# Instruction_Register.net
KiCad netlist of a schematic drawn in EAGLE
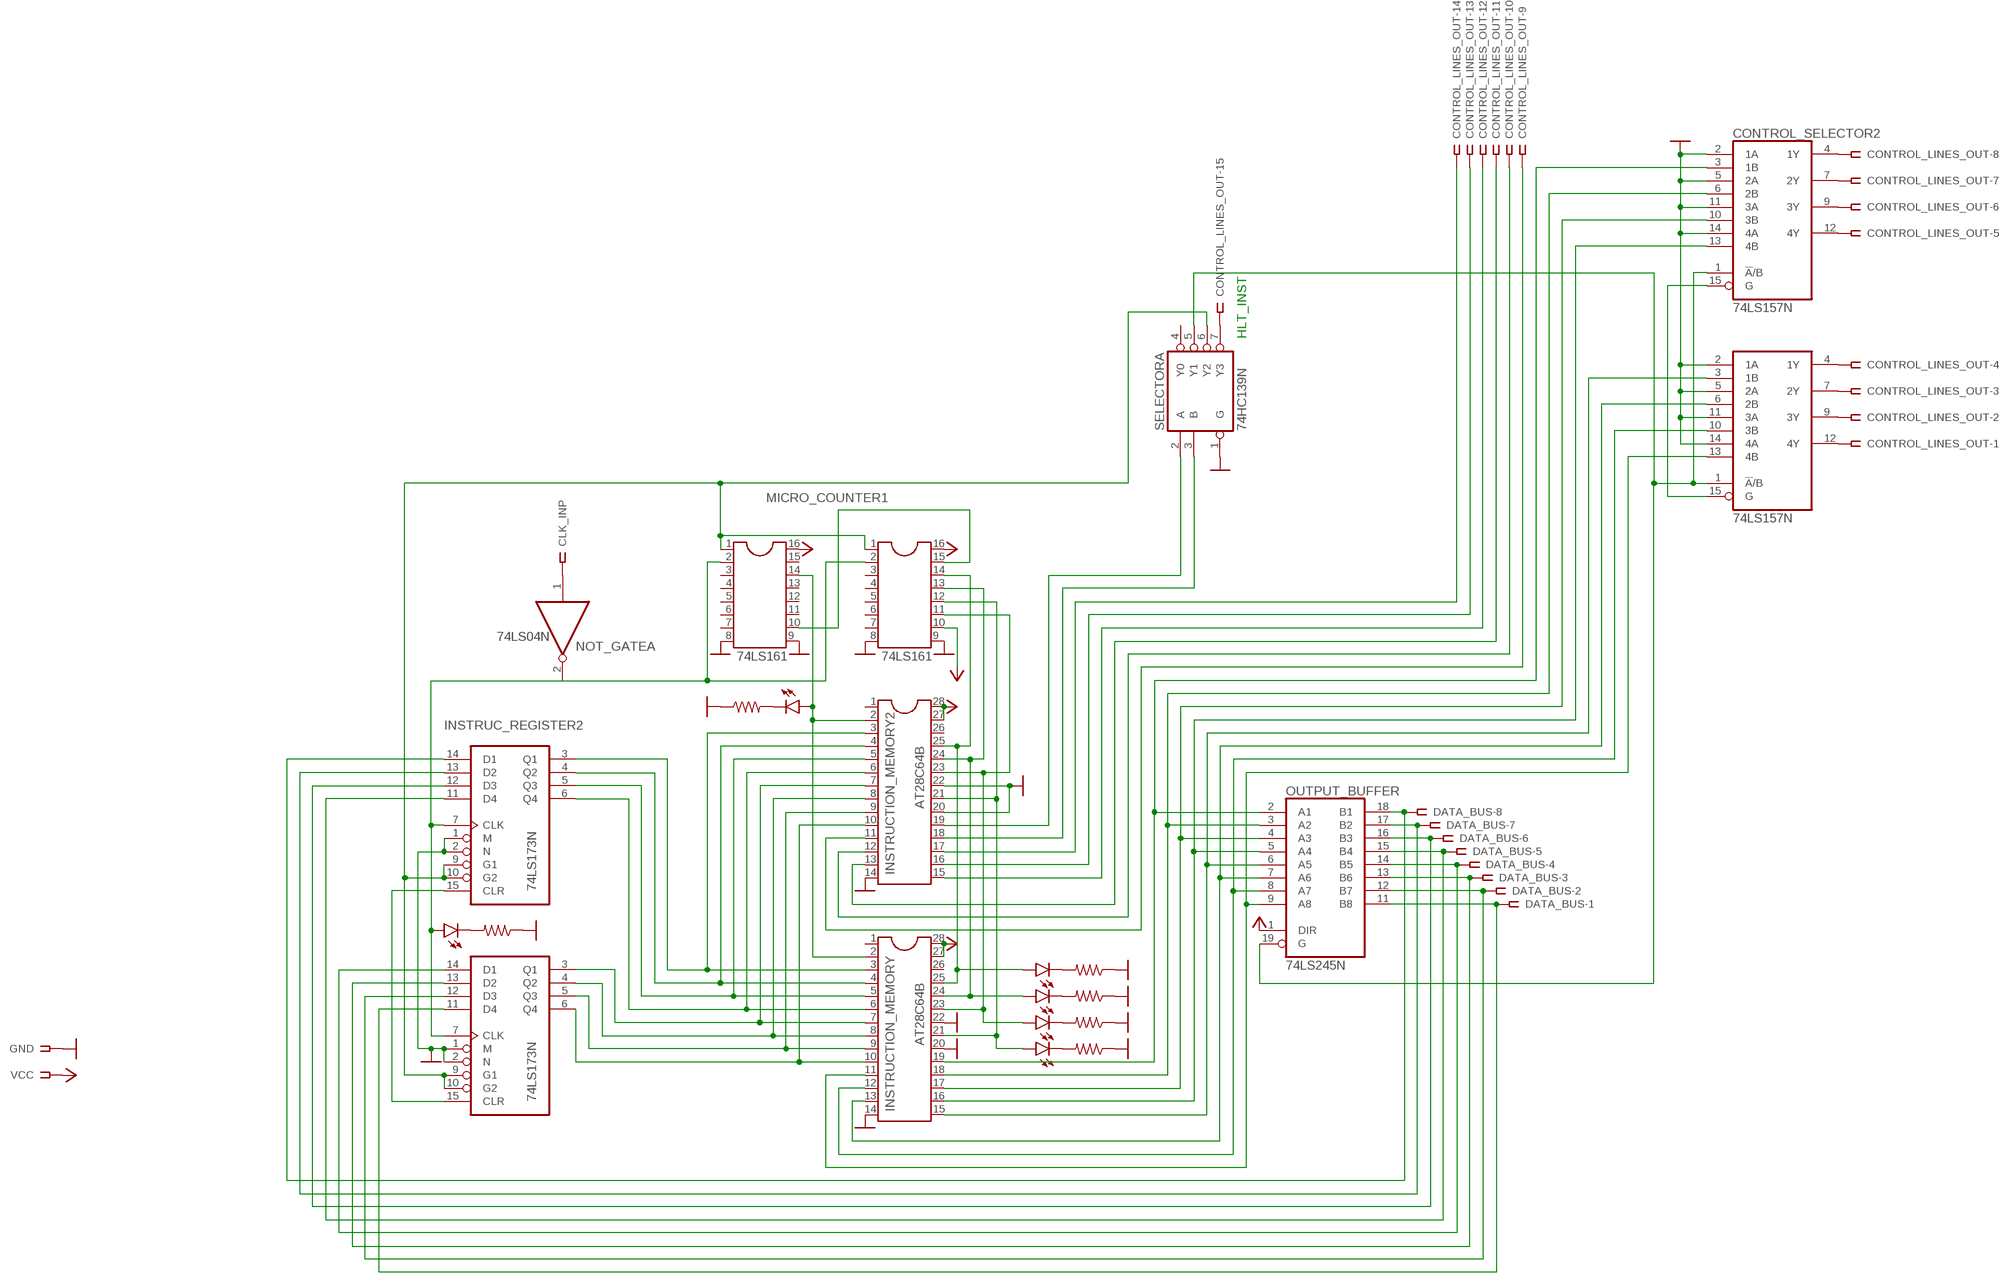
[diagram p0: schematic, sheet 1]

(export (version "E")
  (design (tool "Eeschema 10.0.6"))
  (components
    (comp (ref "CLK_INP")
      (value "SSW-101-02-G-S-RA")
      (footprint "eagle-import:SSW-101-02-G-S-RA")
      (fields (field (name "MF") "Samtec Inc."))
      (libsource (lib "eagle-import") (part "SSW-101-02-G-S-RA"))
    )
    (comp (ref "CONTROL_LINES_OUT")
      (value "SSW-115-02-G-S")
      (footprint "eagle-import:SSW-115-02-G-S")
      (fields (field (name "MF") "Samtec Inc."))
      (libsource (lib "eagle-import") (part "SSW-115-02-G-S"))
    )
    (comp (ref "CONTROL_SELECTOR")
      (value "74LS157N")
      (footprint "eagle-import:DIL16")
      (libsource (lib "eagle-import") (part "74157NLS"))
    )
    (comp (ref "CONTROL_SELECTOR2")
      (value "74LS157N")
      (footprint "eagle-import:DIL16")
      (libsource (lib "eagle-import") (part "74157NLS"))
    )
    (comp (ref "DATA_BUS")
      (value "SSW-108-02-G-S")
      (footprint "eagle-import:SSW-108-02-G-S")
      (fields (field (name "MF") "Samtec Inc."))
      (libsource (lib "eagle-import") (part "SSW-108-02-G-S"))
    )
    (comp (ref "GND")
      (value "SSW-101-02-G-S-RA")
      (footprint "eagle-import:SSW-101-02-G-S-RA")
      (fields (field (name "MF") "Samtec Inc."))
      (libsource (lib "eagle-import") (part "SSW-101-02-G-S-RA"))
    )
    (comp (ref "INSTRUCTION_MEMORY")
      (value "AT28C64B")
      (footprint "eagle-import:DIL28-6")
      (libsource (lib "eagle-import") (part "DIL28"))
    )
    (comp (ref "INSTRUCTION_MEMORY2")
      (value "AT28C64B")
      (footprint "eagle-import:DIL28-6")
      (libsource (lib "eagle-import") (part "DIL28"))
    )
    (comp (ref "INSTRUC_REGISTER2")
      (value "74LS173N")
      (footprint "eagle-import:DIL16")
      (libsource (lib "eagle-import") (part "74173NLS"))
    )
    (comp (ref "INVERTED_CLK")
      (value "LED5MM")
      (footprint "eagle-import:LED5MM")
      (libsource (lib "eagle-import") (part "LED5MM"))
    )
    (comp (ref "I_ADDRESS_REGISTER")
      (value "74LS173N")
      (footprint "eagle-import:DIL16")
      (libsource (lib "eagle-import") (part "74173NLS"))
    )
    (comp (ref "LED18")
      (value "LED5MM")
      (footprint "eagle-import:LED5MM")
      (libsource (lib "eagle-import") (part "LED5MM"))
    )
    (comp (ref "LED19")
      (value "LED5MM")
      (footprint "eagle-import:LED5MM")
      (libsource (lib "eagle-import") (part "LED5MM"))
    )
    (comp (ref "LED20")
      (value "LED5MM")
      (footprint "eagle-import:LED5MM")
      (libsource (lib "eagle-import") (part "LED5MM"))
    )
    (comp (ref "LED21")
      (value "LED5MM")
      (footprint "eagle-import:LED5MM")
      (libsource (lib "eagle-import") (part "LED5MM"))
    )
    (comp (ref "LED22")
      (value "LED5MM")
      (footprint "eagle-import:LED5MM")
      (libsource (lib "eagle-import") (part "LED5MM"))
    )
    (comp (ref "MICRO_COUNTER")
      (value "74LS161")
      (footprint "eagle-import:DIL16")
      (libsource (lib "eagle-import") (part "DIL16"))
    )
    (comp (ref "MICRO_COUNTER1")
      (value "74LS161")
      (footprint "eagle-import:DIL16")
      (libsource (lib "eagle-import") (part "DIL16"))
    )
    (comp (ref "NOT_GATE")
      (value "74LS04N")
      (footprint "eagle-import:DIL14")
      (libsource (lib "eagle-import") (part "7404NLS"))
    )
    (comp (ref "OUTPUT_BUFFER")
      (value "74LS245N")
      (footprint "eagle-import:DIL20")
      (libsource (lib "eagle-import") (part "74245NLS"))
    )
    (comp (ref "R1")
      (value "~220")
      (footprint "eagle-import:0204_7")
      (libsource (lib "eagle-import") (part "R-US_0204/7"))
    )
    (comp (ref "R18")
      (value "~220")
      (footprint "eagle-import:0204_7")
      (libsource (lib "eagle-import") (part "R-US_0204/7"))
    )
    (comp (ref "R19")
      (value "~220")
      (footprint "eagle-import:0204_7")
      (libsource (lib "eagle-import") (part "R-US_0204/7"))
    )
    (comp (ref "R20")
      (value "~220")
      (footprint "eagle-import:0204_7")
      (libsource (lib "eagle-import") (part "R-US_0204/7"))
    )
    (comp (ref "R21")
      (value "~220")
      (footprint "eagle-import:0204_7")
      (libsource (lib "eagle-import") (part "R-US_0204/7"))
    )
    (comp (ref "R22")
      (value "~220")
      (footprint "eagle-import:0204_7")
      (libsource (lib "eagle-import") (part "R-US_0204/7"))
    )
    (comp (ref "SELECTOR")
      (value "74HC139N")
      (footprint "eagle-import:DIL16")
      (libsource (lib "eagle-import") (part "74139NHC"))
    )
    (comp (ref "VCC")
      (value "SSW-101-02-G-S-RA")
      (footprint "eagle-import:SSW-101-02-G-S-RA")
      (fields (field (name "MF") "Samtec Inc."))
      (libsource (lib "eagle-import") (part "SSW-101-02-G-S-RA"))
    )
  )
  (nets
    (net (code "1") (name "GND") (class "Default")
      (node (ref "CONTROL_SELECTOR") (pin "11") (pinfunction "3A_11") (pintype "input"))
      (node (ref "CONTROL_SELECTOR") (pin "14") (pinfunction "4A_14") (pintype "input"))
      (node (ref "CONTROL_SELECTOR") (pin "2") (pinfunction "1A_2") (pintype "input"))
      (node (ref "CONTROL_SELECTOR") (pin "5") (pinfunction "2A_5") (pintype "input"))
      (node (ref "CONTROL_SELECTOR2") (pin "11") (pinfunction "3A_11") (pintype "input"))
      (node (ref "CONTROL_SELECTOR2") (pin "14") (pinfunction "4A_14") (pintype "input"))
      (node (ref "CONTROL_SELECTOR2") (pin "2") (pinfunction "1A_2") (pintype "input"))
      (node (ref "CONTROL_SELECTOR2") (pin "5") (pinfunction "2A_5") (pintype "input"))
      (node (ref "GND") (pin "1") (pinfunction "1_1") (pintype "passive"))
      (node (ref "INSTRUCTION_MEMORY") (pin "14") (pinfunction "14_14") (pintype "passive"))
      (node (ref "INSTRUCTION_MEMORY") (pin "20") (pinfunction "20_20") (pintype "passive"))
      (node (ref "INSTRUCTION_MEMORY") (pin "22") (pinfunction "22_22") (pintype "passive"))
      (node (ref "INSTRUCTION_MEMORY2") (pin "14") (pinfunction "14_14") (pintype "passive"))
      (node (ref "INSTRUCTION_MEMORY2") (pin "20") (pinfunction "20_20") (pintype "passive"))
      (node (ref "INSTRUCTION_MEMORY2") (pin "22") (pinfunction "22_22") (pintype "passive"))
      (node (ref "INSTRUC_REGISTER2") (pin "1") (pinfunction "M_1") (pintype "input"))
      (node (ref "INSTRUC_REGISTER2") (pin "2") (pinfunction "N_2") (pintype "input"))
      (node (ref "I_ADDRESS_REGISTER") (pin "1") (pinfunction "M_1") (pintype "input"))
      (node (ref "I_ADDRESS_REGISTER") (pin "2") (pinfunction "N_2") (pintype "input"))
      (node (ref "MICRO_COUNTER") (pin "8") (pinfunction "8_8") (pintype "passive"))
      (node (ref "MICRO_COUNTER") (pin "9") (pinfunction "9_9") (pintype "passive"))
      (node (ref "MICRO_COUNTER1") (pin "8") (pinfunction "8_8") (pintype "passive"))
      (node (ref "MICRO_COUNTER1") (pin "9") (pinfunction "9_9") (pintype "passive"))
      (node (ref "R1") (pin "1") (pinfunction "1_1") (pintype "passive"))
      (node (ref "R18") (pin "1") (pinfunction "1_1") (pintype "passive"))
      (node (ref "R19") (pin "1") (pinfunction "1_1") (pintype "passive"))
      (node (ref "R20") (pin "1") (pinfunction "1_1") (pintype "passive"))
      (node (ref "R21") (pin "1") (pinfunction "1_1") (pintype "passive"))
      (node (ref "R22") (pin "1") (pinfunction "1_1") (pintype "passive"))
      (node (ref "SELECTOR") (pin "1") (pinfunction "G_1") (pintype "input"))
    )
    (net (code "2") (name "Net-(CONTROL_LINES_OUTB-1)") (class "Default")
      (node (ref "CONTROL_LINES_OUT") (pin "10") (pinfunction "1_10") (pintype "passive"))
      (node (ref "INSTRUCTION_MEMORY2") (pin "12") (pinfunction "12_12") (pintype "passive"))
    )
    (net (code "3") (name "Net-(CONTROL_LINES_OUTC-1)") (class "Default")
      (node (ref "CONTROL_LINES_OUT") (pin "11") (pinfunction "1_11") (pintype "passive"))
      (node (ref "INSTRUCTION_MEMORY2") (pin "13") (pinfunction "13_13") (pintype "passive"))
    )
    (net (code "4") (name "Net-(CONTROL_LINES_OUTD-1)") (class "Default")
      (node (ref "CONTROL_LINES_OUT") (pin "12") (pinfunction "1_12") (pintype "passive"))
      (node (ref "INSTRUCTION_MEMORY2") (pin "15") (pinfunction "15_15") (pintype "passive"))
    )
    (net (code "5") (name "Net-(CONTROL_LINES_OUTE-1)") (class "Default")
      (node (ref "CONTROL_LINES_OUT") (pin "13") (pinfunction "1_13") (pintype "passive"))
      (node (ref "INSTRUCTION_MEMORY2") (pin "16") (pinfunction "16_16") (pintype "passive"))
    )
    (net (code "6") (name "Net-(CONTROL_LINES_OUTF-1)") (class "Default")
      (node (ref "CONTROL_LINES_OUT") (pin "14") (pinfunction "1_14") (pintype "passive"))
      (node (ref "INSTRUCTION_MEMORY2") (pin "17") (pinfunction "17_17") (pintype "passive"))
    )
    (net (code "7") (name "Net-(CONTROL_LINES_OUTG-1)") (class "Default")
      (node (ref "CONTROL_LINES_OUT") (pin "15") (pinfunction "1_15") (pintype "passive"))
      (node (ref "SELECTOR") (pin "7") (pinfunction "Y3_7") (pintype "output"))
    )
    (net (code "8") (name "Net-(CONTROL_LINES_OUTH-1)") (class "Default")
      (node (ref "CONTROL_LINES_OUT") (pin "2") (pinfunction "1_2") (pintype "passive"))
      (node (ref "CONTROL_SELECTOR") (pin "9") (pinfunction "3Y_9") (pintype "output"))
    )
    (net (code "9") (name "Net-(CONTROL_LINES_OUTI-1)") (class "Default")
      (node (ref "CONTROL_LINES_OUT") (pin "3") (pinfunction "1_3") (pintype "passive"))
      (node (ref "CONTROL_SELECTOR") (pin "7") (pinfunction "2Y_7") (pintype "output"))
    )
    (net (code "10") (name "Net-(CONTROL_LINES_OUTJ-1)") (class "Default")
      (node (ref "CONTROL_LINES_OUT") (pin "4") (pinfunction "1_4") (pintype "passive"))
      (node (ref "CONTROL_SELECTOR") (pin "4") (pinfunction "1Y_4") (pintype "output"))
    )
    (net (code "11") (name "Net-(CONTROL_LINES_OUTK-1)") (class "Default")
      (node (ref "CONTROL_LINES_OUT") (pin "5") (pinfunction "1_5") (pintype "passive"))
      (node (ref "CONTROL_SELECTOR2") (pin "12") (pinfunction "4Y_12") (pintype "output"))
    )
    (net (code "12") (name "Net-(CONTROL_LINES_OUTL-1)") (class "Default")
      (node (ref "CONTROL_LINES_OUT") (pin "6") (pinfunction "1_6") (pintype "passive"))
      (node (ref "CONTROL_SELECTOR2") (pin "9") (pinfunction "3Y_9") (pintype "output"))
    )
    (net (code "13") (name "Net-(CONTROL_LINES_OUTM-1)") (class "Default")
      (node (ref "CONTROL_LINES_OUT") (pin "7") (pinfunction "1_7") (pintype "passive"))
      (node (ref "CONTROL_SELECTOR2") (pin "7") (pinfunction "2Y_7") (pintype "output"))
    )
    (net (code "14") (name "Net-(CONTROL_LINES_OUTN-1)") (class "Default")
      (node (ref "CONTROL_LINES_OUT") (pin "8") (pinfunction "1_8") (pintype "passive"))
      (node (ref "CONTROL_SELECTOR2") (pin "4") (pinfunction "1Y_4") (pintype "output"))
    )
    (net (code "15") (name "Net-(CONTROL_LINES_OUTO-1)") (class "Default")
      (node (ref "CONTROL_LINES_OUT") (pin "9") (pinfunction "1_9") (pintype "passive"))
      (node (ref "INSTRUCTION_MEMORY2") (pin "11") (pinfunction "11_11") (pintype "passive"))
    )
    (net (code "16") (name "Net-(CONTROL_SELECTOR2A-1B)") (class "Default")
      (node (ref "CONTROL_SELECTOR2") (pin "3") (pinfunction "1B_3") (pintype "input"))
      (node (ref "INSTRUCTION_MEMORY") (pin "19") (pinfunction "19_19") (pintype "passive"))
      (node (ref "OUTPUT_BUFFER") (pin "2") (pinfunction "A1_2") (pintype "bidirectional"))
    )
    (net (code "17") (name "Net-(CONTROL_SELECTOR2A-2B)") (class "Default")
      (node (ref "CONTROL_SELECTOR2") (pin "6") (pinfunction "2B_6") (pintype "input"))
      (node (ref "INSTRUCTION_MEMORY") (pin "18") (pinfunction "18_18") (pintype "passive"))
      (node (ref "OUTPUT_BUFFER") (pin "3") (pinfunction "A2_3") (pintype "bidirectional"))
    )
    (net (code "18") (name "Net-(CONTROL_SELECTOR2A-3B)") (class "Default")
      (node (ref "CONTROL_SELECTOR2") (pin "10") (pinfunction "3B_10") (pintype "input"))
      (node (ref "INSTRUCTION_MEMORY") (pin "17") (pinfunction "17_17") (pintype "passive"))
      (node (ref "OUTPUT_BUFFER") (pin "4") (pinfunction "A3_4") (pintype "bidirectional"))
    )
    (net (code "19") (name "Net-(CONTROL_SELECTOR2A-4B)") (class "Default")
      (node (ref "CONTROL_SELECTOR2") (pin "13") (pinfunction "4B_13") (pintype "input"))
      (node (ref "INSTRUCTION_MEMORY") (pin "16") (pinfunction "16_16") (pintype "passive"))
      (node (ref "OUTPUT_BUFFER") (pin "5") (pinfunction "A4_5") (pintype "bidirectional"))
    )
    (net (code "20") (name "Net-(CONTROL_SELECTOR2A-G)") (class "Default")
      (node (ref "CONTROL_SELECTOR") (pin "15") (pinfunction "G_15") (pintype "input"))
      (node (ref "CONTROL_SELECTOR2") (pin "15") (pinfunction "G_15") (pintype "input"))
    )
    (net (code "21") (name "Net-(CONTROL_SELECTOR2A-~{A}{slash}B)") (class "Default")
      (node (ref "CONTROL_SELECTOR") (pin "1") (pinfunction "~{A}/B_1") (pintype "input"))
      (node (ref "CONTROL_SELECTOR2") (pin "1") (pinfunction "~{A}/B_1") (pintype "input"))
      (node (ref "OUTPUT_BUFFER") (pin "19") (pinfunction "G_19") (pintype "input"))
      (node (ref "SELECTOR") (pin "5") (pinfunction "Y1_5") (pintype "output"))
    )
    (net (code "22") (name "Net-(CONTROL_SELECTORA-1B)") (class "Default")
      (node (ref "CONTROL_SELECTOR") (pin "3") (pinfunction "1B_3") (pintype "input"))
      (node (ref "INSTRUCTION_MEMORY") (pin "15") (pinfunction "15_15") (pintype "passive"))
      (node (ref "OUTPUT_BUFFER") (pin "6") (pinfunction "A5_6") (pintype "bidirectional"))
    )
    (net (code "23") (name "Net-(CONTROL_SELECTORA-2B)") (class "Default")
      (node (ref "CONTROL_SELECTOR") (pin "6") (pinfunction "2B_6") (pintype "input"))
      (node (ref "INSTRUCTION_MEMORY") (pin "13") (pinfunction "13_13") (pintype "passive"))
      (node (ref "OUTPUT_BUFFER") (pin "7") (pinfunction "A6_7") (pintype "bidirectional"))
    )
    (net (code "24") (name "Net-(CONTROL_SELECTORA-3B)") (class "Default")
      (node (ref "CONTROL_SELECTOR") (pin "10") (pinfunction "3B_10") (pintype "input"))
      (node (ref "INSTRUCTION_MEMORY") (pin "12") (pinfunction "12_12") (pintype "passive"))
      (node (ref "OUTPUT_BUFFER") (pin "8") (pinfunction "A7_8") (pintype "bidirectional"))
    )
    (net (code "25") (name "Net-(CONTROL_SELECTORA-4B)") (class "Default")
      (node (ref "CONTROL_SELECTOR") (pin "13") (pinfunction "4B_13") (pintype "input"))
      (node (ref "INSTRUCTION_MEMORY") (pin "11") (pinfunction "11_11") (pintype "passive"))
      (node (ref "OUTPUT_BUFFER") (pin "9") (pinfunction "A8_9") (pintype "bidirectional"))
    )
    (net (code "26") (name "Net-(CONTROL_SELECTORA-4Y)") (class "Default")
      (node (ref "CONTROL_LINES_OUT") (pin "1") (pinfunction "1_1") (pintype "passive"))
      (node (ref "CONTROL_SELECTOR") (pin "12") (pinfunction "4Y_12") (pintype "output"))
    )
    (net (code "27") (name "Net-(DATA_BUSB-1)") (class "Default")
      (node (ref "DATA_BUS") (pin "2") (pinfunction "1_2") (pintype "passive"))
      (node (ref "I_ADDRESS_REGISTER") (pin "12") (pinfunction "D3_12") (pintype "input"))
      (node (ref "OUTPUT_BUFFER") (pin "12") (pinfunction "B7_12") (pintype "bidirectional"))
    )
    (net (code "28") (name "Net-(DATA_BUSC-1)") (class "Default")
      (node (ref "DATA_BUS") (pin "3") (pinfunction "1_3") (pintype "passive"))
      (node (ref "I_ADDRESS_REGISTER") (pin "13") (pinfunction "D2_13") (pintype "input"))
      (node (ref "OUTPUT_BUFFER") (pin "13") (pinfunction "B6_13") (pintype "bidirectional"))
    )
    (net (code "29") (name "Net-(DATA_BUSD-1)") (class "Default")
      (node (ref "DATA_BUS") (pin "4") (pinfunction "1_4") (pintype "passive"))
      (node (ref "I_ADDRESS_REGISTER") (pin "14") (pinfunction "D1_14") (pintype "input"))
      (node (ref "OUTPUT_BUFFER") (pin "14") (pinfunction "B5_14") (pintype "bidirectional"))
    )
    (net (code "30") (name "Net-(DATA_BUSE-1)") (class "Default")
      (node (ref "DATA_BUS") (pin "5") (pinfunction "1_5") (pintype "passive"))
      (node (ref "INSTRUC_REGISTER2") (pin "11") (pinfunction "D4_11") (pintype "input"))
      (node (ref "OUTPUT_BUFFER") (pin "15") (pinfunction "B4_15") (pintype "bidirectional"))
    )
    (net (code "31") (name "Net-(DATA_BUSF-1)") (class "Default")
      (node (ref "DATA_BUS") (pin "6") (pinfunction "1_6") (pintype "passive"))
      (node (ref "INSTRUC_REGISTER2") (pin "12") (pinfunction "D3_12") (pintype "input"))
      (node (ref "OUTPUT_BUFFER") (pin "16") (pinfunction "B3_16") (pintype "bidirectional"))
    )
    (net (code "32") (name "Net-(DATA_BUSG-1)") (class "Default")
      (node (ref "DATA_BUS") (pin "7") (pinfunction "1_7") (pintype "passive"))
      (node (ref "INSTRUC_REGISTER2") (pin "13") (pinfunction "D2_13") (pintype "input"))
      (node (ref "OUTPUT_BUFFER") (pin "17") (pinfunction "B2_17") (pintype "bidirectional"))
    )
    (net (code "33") (name "Net-(DATA_BUSH-1)") (class "Default")
      (node (ref "DATA_BUS") (pin "8") (pinfunction "1_8") (pintype "passive"))
      (node (ref "INSTRUC_REGISTER2") (pin "14") (pinfunction "D1_14") (pintype "input"))
      (node (ref "OUTPUT_BUFFER") (pin "18") (pinfunction "B1_18") (pintype "bidirectional"))
    )
    (net (code "34") (name "Net-(INSTRUCTION_MEMORY-Pad2)") (class "Default")
      (node (ref "INSTRUCTION_MEMORY") (pin "2") (pinfunction "2_2") (pintype "passive"))
      (node (ref "INSTRUCTION_MEMORY2") (pin "2") (pinfunction "2_2") (pintype "passive"))
      (node (ref "LED22") (pin "A") (pinfunction "A_A") (pintype "passive"))
      (node (ref "MICRO_COUNTER1") (pin "14") (pinfunction "14_14") (pintype "passive"))
    )
    (net (code "35") (name "Net-(INSTRUCTION_MEMORY-Pad21)") (class "Default")
      (node (ref "INSTRUCTION_MEMORY") (pin "21") (pinfunction "21_21") (pintype "passive"))
      (node (ref "INSTRUCTION_MEMORY2") (pin "21") (pinfunction "21_21") (pintype "passive"))
      (node (ref "LED21") (pin "A") (pinfunction "A_A") (pintype "passive"))
      (node (ref "MICRO_COUNTER") (pin "12") (pinfunction "12_12") (pintype "passive"))
    )
    (net (code "36") (name "Net-(INSTRUCTION_MEMORY-Pad23)") (class "Default")
      (node (ref "INSTRUCTION_MEMORY") (pin "23") (pinfunction "23_23") (pintype "passive"))
      (node (ref "INSTRUCTION_MEMORY2") (pin "23") (pinfunction "23_23") (pintype "passive"))
      (node (ref "LED20") (pin "A") (pinfunction "A_A") (pintype "passive"))
      (node (ref "MICRO_COUNTER") (pin "11") (pinfunction "11_11") (pintype "passive"))
    )
    (net (code "37") (name "Net-(INSTRUCTION_MEMORY-Pad24)") (class "Default")
      (node (ref "INSTRUCTION_MEMORY") (pin "24") (pinfunction "24_24") (pintype "passive"))
      (node (ref "INSTRUCTION_MEMORY2") (pin "24") (pinfunction "24_24") (pintype "passive"))
      (node (ref "LED19") (pin "A") (pinfunction "A_A") (pintype "passive"))
      (node (ref "MICRO_COUNTER") (pin "13") (pinfunction "13_13") (pintype "passive"))
    )
    (net (code "38") (name "Net-(INSTRUCTION_MEMORY-Pad25)") (class "Default")
      (node (ref "INSTRUCTION_MEMORY") (pin "25") (pinfunction "25_25") (pintype "passive"))
      (node (ref "INSTRUCTION_MEMORY2") (pin "25") (pinfunction "25_25") (pintype "passive"))
      (node (ref "LED18") (pin "A") (pinfunction "A_A") (pintype "passive"))
      (node (ref "MICRO_COUNTER") (pin "14") (pinfunction "14_14") (pintype "passive"))
    )
    (net (code "39") (name "Net-(INSTRUC_REGISTER2A-CLK)") (class "Default")
      (node (ref "INSTRUC_REGISTER2") (pin "7") (pinfunction "CLK_7") (pintype "input"))
      (node (ref "INVERTED_CLK") (pin "A") (pinfunction "A_A") (pintype "passive"))
      (node (ref "I_ADDRESS_REGISTER") (pin "7") (pinfunction "CLK_7") (pintype "input"))
      (node (ref "MICRO_COUNTER") (pin "2") (pinfunction "2_2") (pintype "passive"))
      (node (ref "MICRO_COUNTER1") (pin "2") (pinfunction "2_2") (pintype "passive"))
      (node (ref "NOT_GATE") (pin "2") (pinfunction "O_2") (pintype "output"))
    )
    (net (code "40") (name "Net-(INSTRUC_REGISTER2A-CLR)") (class "Default")
      (node (ref "INSTRUC_REGISTER2") (pin "15") (pinfunction "CLR_15") (pintype "input"))
      (node (ref "I_ADDRESS_REGISTER") (pin "15") (pinfunction "CLR_15") (pintype "input"))
    )
    (net (code "41") (name "Net-(INSTRUC_REGISTER2A-G1)") (class "Default")
      (node (ref "INSTRUC_REGISTER2") (pin "10") (pinfunction "G2_10") (pintype "input"))
      (node (ref "INSTRUC_REGISTER2") (pin "9") (pinfunction "G1_9") (pintype "input"))
      (node (ref "I_ADDRESS_REGISTER") (pin "10") (pinfunction "G2_10") (pintype "input"))
      (node (ref "I_ADDRESS_REGISTER") (pin "9") (pinfunction "G1_9") (pintype "input"))
      (node (ref "MICRO_COUNTER") (pin "1") (pinfunction "1_1") (pintype "passive"))
      (node (ref "MICRO_COUNTER1") (pin "1") (pinfunction "1_1") (pintype "passive"))
      (node (ref "SELECTOR") (pin "6") (pinfunction "Y2_6") (pintype "output"))
    )
    (net (code "42") (name "Net-(INSTRUC_REGISTER2A-Q1)") (class "Default")
      (node (ref "INSTRUCTION_MEMORY") (pin "3") (pinfunction "3_3") (pintype "passive"))
      (node (ref "INSTRUCTION_MEMORY2") (pin "3") (pinfunction "3_3") (pintype "passive"))
      (node (ref "INSTRUC_REGISTER2") (pin "3") (pinfunction "Q1_3") (pintype "tri_state"))
    )
    (net (code "43") (name "Net-(INSTRUC_REGISTER2A-Q2)") (class "Default")
      (node (ref "INSTRUCTION_MEMORY") (pin "4") (pinfunction "4_4") (pintype "passive"))
      (node (ref "INSTRUCTION_MEMORY2") (pin "4") (pinfunction "4_4") (pintype "passive"))
      (node (ref "INSTRUC_REGISTER2") (pin "4") (pinfunction "Q2_4") (pintype "tri_state"))
    )
    (net (code "44") (name "Net-(INSTRUC_REGISTER2A-Q3)") (class "Default")
      (node (ref "INSTRUCTION_MEMORY") (pin "5") (pinfunction "5_5") (pintype "passive"))
      (node (ref "INSTRUCTION_MEMORY2") (pin "5") (pinfunction "5_5") (pintype "passive"))
      (node (ref "INSTRUC_REGISTER2") (pin "5") (pinfunction "Q3_5") (pintype "tri_state"))
    )
    (net (code "45") (name "Net-(INSTRUC_REGISTER2A-Q4)") (class "Default")
      (node (ref "INSTRUCTION_MEMORY") (pin "6") (pinfunction "6_6") (pintype "passive"))
      (node (ref "INSTRUCTION_MEMORY2") (pin "6") (pinfunction "6_6") (pintype "passive"))
      (node (ref "INSTRUC_REGISTER2") (pin "6") (pinfunction "Q4_6") (pintype "tri_state"))
    )
    (net (code "46") (name "Net-(INVERTED_CLK-C)") (class "Default")
      (node (ref "INVERTED_CLK") (pin "K") (pinfunction "C_K") (pintype "passive"))
      (node (ref "R1") (pin "2") (pinfunction "2_2") (pintype "passive"))
    )
    (net (code "47") (name "Net-(I_ADDRESS_REGISTERA-D4)") (class "Default")
      (node (ref "DATA_BUS") (pin "1") (pinfunction "1_1") (pintype "passive"))
      (node (ref "I_ADDRESS_REGISTER") (pin "11") (pinfunction "D4_11") (pintype "input"))
      (node (ref "OUTPUT_BUFFER") (pin "11") (pinfunction "B8_11") (pintype "bidirectional"))
    )
    (net (code "48") (name "Net-(I_ADDRESS_REGISTERA-Q1)") (class "Default")
      (node (ref "INSTRUCTION_MEMORY") (pin "7") (pinfunction "7_7") (pintype "passive"))
      (node (ref "INSTRUCTION_MEMORY2") (pin "7") (pinfunction "7_7") (pintype "passive"))
      (node (ref "I_ADDRESS_REGISTER") (pin "3") (pinfunction "Q1_3") (pintype "tri_state"))
    )
    (net (code "49") (name "Net-(I_ADDRESS_REGISTERA-Q2)") (class "Default")
      (node (ref "INSTRUCTION_MEMORY") (pin "8") (pinfunction "8_8") (pintype "passive"))
      (node (ref "INSTRUCTION_MEMORY2") (pin "8") (pinfunction "8_8") (pintype "passive"))
      (node (ref "I_ADDRESS_REGISTER") (pin "4") (pinfunction "Q2_4") (pintype "tri_state"))
    )
    (net (code "50") (name "Net-(I_ADDRESS_REGISTERA-Q3)") (class "Default")
      (node (ref "INSTRUCTION_MEMORY") (pin "9") (pinfunction "9_9") (pintype "passive"))
      (node (ref "INSTRUCTION_MEMORY2") (pin "9") (pinfunction "9_9") (pintype "passive"))
      (node (ref "I_ADDRESS_REGISTER") (pin "5") (pinfunction "Q3_5") (pintype "tri_state"))
    )
    (net (code "51") (name "Net-(I_ADDRESS_REGISTERA-Q4)") (class "Default")
      (node (ref "INSTRUCTION_MEMORY") (pin "10") (pinfunction "10_10") (pintype "passive"))
      (node (ref "INSTRUCTION_MEMORY2") (pin "10") (pinfunction "10_10") (pintype "passive"))
      (node (ref "I_ADDRESS_REGISTER") (pin "6") (pinfunction "Q4_6") (pintype "tri_state"))
    )
    (net (code "52") (name "Net-(LED18-C)") (class "Default")
      (node (ref "LED18") (pin "K") (pinfunction "C_K") (pintype "passive"))
      (node (ref "R18") (pin "2") (pinfunction "2_2") (pintype "passive"))
    )
    (net (code "53") (name "Net-(LED19-C)") (class "Default")
      (node (ref "LED19") (pin "K") (pinfunction "C_K") (pintype "passive"))
      (node (ref "R19") (pin "2") (pinfunction "2_2") (pintype "passive"))
    )
    (net (code "54") (name "Net-(LED20-C)") (class "Default")
      (node (ref "LED20") (pin "K") (pinfunction "C_K") (pintype "passive"))
      (node (ref "R20") (pin "2") (pinfunction "2_2") (pintype "passive"))
    )
    (net (code "55") (name "Net-(LED21-C)") (class "Default")
      (node (ref "LED21") (pin "K") (pinfunction "C_K") (pintype "passive"))
      (node (ref "R21") (pin "2") (pinfunction "2_2") (pintype "passive"))
    )
    (net (code "56") (name "Net-(LED22-C)") (class "Default")
      (node (ref "LED22") (pin "K") (pinfunction "C_K") (pintype "passive"))
      (node (ref "R22") (pin "2") (pinfunction "2_2") (pintype "passive"))
    )
    (net (code "57") (name "Net-(MICRO_COUNTER-Pad15)") (class "Default")
      (node (ref "MICRO_COUNTER") (pin "15") (pinfunction "15_15") (pintype "passive"))
      (node (ref "MICRO_COUNTER1") (pin "10") (pinfunction "10_10") (pintype "passive"))
    )
    (net (code "58") (name "Net-(NOT_GATEA-I)") (class "Default")
      (node (ref "CLK_INP") (pin "1") (pinfunction "1_1") (pintype "passive"))
      (node (ref "NOT_GATE") (pin "1") (pinfunction "I_1") (pintype "input"))
    )
    (net (code "59") (name "Net-(SELECTORA-A)") (class "Default")
      (node (ref "INSTRUCTION_MEMORY2") (pin "19") (pinfunction "19_19") (pintype "passive"))
      (node (ref "SELECTOR") (pin "2") (pinfunction "A_2") (pintype "input"))
    )
    (net (code "60") (name "Net-(SELECTORA-B)") (class "Default")
      (node (ref "INSTRUCTION_MEMORY2") (pin "18") (pinfunction "18_18") (pintype "passive"))
      (node (ref "SELECTOR") (pin "3") (pinfunction "B_3") (pintype "input"))
    )
    (net (code "61") (name "VCC") (class "Default")
      (node (ref "INSTRUCTION_MEMORY") (pin "27") (pinfunction "27_27") (pintype "passive"))
      (node (ref "INSTRUCTION_MEMORY") (pin "28") (pinfunction "28_28") (pintype "passive"))
      (node (ref "INSTRUCTION_MEMORY2") (pin "27") (pinfunction "27_27") (pintype "passive"))
      (node (ref "INSTRUCTION_MEMORY2") (pin "28") (pinfunction "28_28") (pintype "passive"))
      (node (ref "MICRO_COUNTER") (pin "10") (pinfunction "10_10") (pintype "passive"))
      (node (ref "MICRO_COUNTER") (pin "16") (pinfunction "16_16") (pintype "passive"))
      (node (ref "MICRO_COUNTER1") (pin "16") (pinfunction "16_16") (pintype "passive"))
      (node (ref "OUTPUT_BUFFER") (pin "1") (pinfunction "DIR_1") (pintype "input"))
      (node (ref "VCC") (pin "1") (pinfunction "1_1") (pintype "passive"))
    )
    (net (code "62") (name "unconnected-(INSTRUCTION_MEMORY-Pad1)") (class "Default")
      (node (ref "INSTRUCTION_MEMORY") (pin "1") (pinfunction "1_1") (pintype "passive"))
    )
    (net (code "63") (name "unconnected-(INSTRUCTION_MEMORY-Pad26)") (class "Default")
      (node (ref "INSTRUCTION_MEMORY") (pin "26") (pinfunction "26_26") (pintype "passive"))
    )
    (net (code "64") (name "unconnected-(INSTRUCTION_MEMORY2-Pad1)") (class "Default")
      (node (ref "INSTRUCTION_MEMORY2") (pin "1") (pinfunction "1_1") (pintype "passive"))
    )
    (net (code "65") (name "unconnected-(INSTRUCTION_MEMORY2-Pad26)") (class "Default")
      (node (ref "INSTRUCTION_MEMORY2") (pin "26") (pinfunction "26_26") (pintype "passive"))
    )
    (net (code "66") (name "unconnected-(MICRO_COUNTER-Pad3)") (class "Default")
      (node (ref "MICRO_COUNTER") (pin "3") (pinfunction "3_3") (pintype "passive"))
    )
    (net (code "67") (name "unconnected-(MICRO_COUNTER-Pad4)") (class "Default")
      (node (ref "MICRO_COUNTER") (pin "4") (pinfunction "4_4") (pintype "passive"))
    )
    (net (code "68") (name "unconnected-(MICRO_COUNTER-Pad5)") (class "Default")
      (node (ref "MICRO_COUNTER") (pin "5") (pinfunction "5_5") (pintype "passive"))
    )
    (net (code "69") (name "unconnected-(MICRO_COUNTER-Pad6)") (class "Default")
      (node (ref "MICRO_COUNTER") (pin "6") (pinfunction "6_6") (pintype "passive"))
    )
    (net (code "70") (name "unconnected-(MICRO_COUNTER-Pad7)") (class "Default")
      (node (ref "MICRO_COUNTER") (pin "7") (pinfunction "7_7") (pintype "passive"))
    )
    (net (code "71") (name "unconnected-(MICRO_COUNTER1-Pad3)") (class "Default")
      (node (ref "MICRO_COUNTER1") (pin "3") (pinfunction "3_3") (pintype "passive"))
    )
    (net (code "72") (name "unconnected-(MICRO_COUNTER1-Pad4)") (class "Default")
      (node (ref "MICRO_COUNTER1") (pin "4") (pinfunction "4_4") (pintype "passive"))
    )
    (net (code "73") (name "unconnected-(MICRO_COUNTER1-Pad5)") (class "Default")
      (node (ref "MICRO_COUNTER1") (pin "5") (pinfunction "5_5") (pintype "passive"))
    )
    (net (code "74") (name "unconnected-(MICRO_COUNTER1-Pad6)") (class "Default")
      (node (ref "MICRO_COUNTER1") (pin "6") (pinfunction "6_6") (pintype "passive"))
    )
    (net (code "75") (name "unconnected-(MICRO_COUNTER1-Pad7)") (class "Default")
      (node (ref "MICRO_COUNTER1") (pin "7") (pinfunction "7_7") (pintype "passive"))
    )
    (net (code "76") (name "unconnected-(MICRO_COUNTER1-Pad11)") (class "Default")
      (node (ref "MICRO_COUNTER1") (pin "11") (pinfunction "11_11") (pintype "passive"))
    )
    (net (code "77") (name "unconnected-(MICRO_COUNTER1-Pad12)") (class "Default")
      (node (ref "MICRO_COUNTER1") (pin "12") (pinfunction "12_12") (pintype "passive"))
    )
    (net (code "78") (name "unconnected-(MICRO_COUNTER1-Pad13)") (class "Default")
      (node (ref "MICRO_COUNTER1") (pin "13") (pinfunction "13_13") (pintype "passive"))
    )
    (net (code "79") (name "unconnected-(MICRO_COUNTER1-Pad15)") (class "Default")
      (node (ref "MICRO_COUNTER1") (pin "15") (pinfunction "15_15") (pintype "passive"))
    )
    (net (code "80") (name "unconnected-(SELECTORA-Y0-Pad4)") (class "Default")
      (node (ref "SELECTOR") (pin "4") (pinfunction "Y0_4") (pintype "output"))
    )
  )
)
